# main.net
KiCad netlist of a schematic drawn in Altium Designer
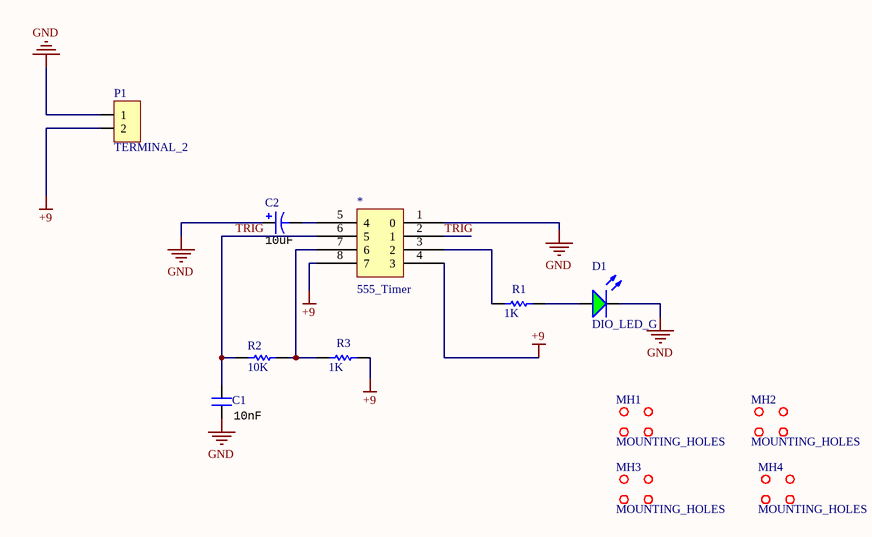
[diagram p0: main.SchDoc]

(export (version "E")
  (design (tool "Eeschema 10.0.6"))
  (components
    (comp (ref "*") (value "555_Timer") (libsource (lib "UWRT_Schematic_Library_2020") (part "555_Timer")))
    (comp (ref "C1")
      (value "10nF")
      (footprint "CAPC0603(1608)55_N")
      (description "CAP CER 10000PF 16V X7R 0603")
      (fields (field (name "MPN") "CC0603KRX7R7BB103") (field (name "MANUFACTURER") "Yageo"))
      (libsource (lib "UWRT_Schematic_Library_2020") (part "CAP_10nF_0603"))
    )
    (comp (ref "C2")
      (value "10uF")
      (footprint "AVX-CAPC3528_V")
      (description "CAP TANT 10UF 20% 10V 1411")
      (fields (field (name "MPN") "F971A106MBAHT3") (field (name "MANUFACTURER") "AVX Corporation"))
      (libsource (lib "UWRT_Schematic_Library_2020") (part "CAP_10uF_1411_POL"))
    )
    (comp (ref "D1")
      (value "DIO_LED_G")
      (footprint "LED_0805_LINE")
      (description "LED GREEN DIFFUSED 0805 SMD")
      (fields (field (name "MPN") "LG R971-KN-1") (field (name "MANUFACTURER") "OSRAM"))
      (libsource (lib "UWRT_Schematic_Library_2020") (part "DIO_LED_G"))
    )
    (comp (ref "MH1")
      (value "MOUNTING_HOLES")
      (footprint "MOUNTING_HOLE")
      (description "6cm x 6cm")
      (libsource (lib "UWRT_Schematic_Library_2020") (part "MOUNTING_HOLES"))
    )
    (comp (ref "MH2")
      (value "MOUNTING_HOLES")
      (footprint "MOUNTING_HOLE")
      (description "6cm x 6cm")
      (libsource (lib "UWRT_Schematic_Library_2020") (part "MOUNTING_HOLES"))
    )
    (comp (ref "MH3")
      (value "MOUNTING_HOLES")
      (footprint "MOUNTING_HOLE")
      (description "6cm x 6cm")
      (libsource (lib "UWRT_Schematic_Library_2020") (part "MOUNTING_HOLES"))
    )
    (comp (ref "MH4")
      (value "MOUNTING_HOLES")
      (footprint "MOUNTING_HOLE")
      (description "6cm x 6cm")
      (libsource (lib "UWRT_Schematic_Library_2020") (part "MOUNTING_HOLES"))
    )
    (comp (ref "P1")
      (value "TERMINAL_2")
      (footprint "OSTYK51102030")
      (description "Header, 2-Pin")
      (fields (field (name "MPN") "OSTYK51102030") (field (name "DIGIKEY PART NUMBER") "ED2953-ND"))
      (libsource (lib "UWRT_Schematic_Library_2020") (part "TERMINAL_2"))
    )
    (comp (ref "R1")
      (value "1K")
      (footprint "RESC0603(1608)_N")
      (description "RES SMD 1K OHM 5% 1/10W 0603")
      (fields (field (name "TOLERANCE") "5%") (field (name "MANUFACTURER") "Yageo"))
      (libsource (lib "UWRT_Schematic_Library_2020") (part "RES_1K_0603"))
    )
    (comp (ref "R2")
      (value "10K")
      (footprint "RESC0603(1608)_N")
      (description "RES SMD 10K OHM 5% 1/10W 0603")
      (fields (field (name "MANUFACTURER") "Yageo") (field (name "MPN") "RC0603JR-0710KL"))
      (libsource (lib "UWRT_Schematic_Library_2020") (part "RES_10K_0603"))
    )
    (comp (ref "R3")
      (value "1K")
      (footprint "RESC0603(1608)_N")
      (description "RES SMD 1K OHM 5% 1/10W 0603")
      (fields (field (name "TOLERANCE") "5%") (field (name "MANUFACTURER") "Yageo"))
      (libsource (lib "UWRT_Schematic_Library_2020") (part "RES_1K_0603"))
    )
  )
  (nets
    (net (code "1") (name "+9") (class "Default")
      (node (ref "*") (pin "4") (pinfunction "3_4") (pintype "passive"))
      (node (ref "*") (pin "8") (pinfunction "7_8") (pintype "passive"))
      (node (ref "P1") (pin "2") (pinfunction "2_2") (pintype "passive"))
      (node (ref "R3") (pin "2") (pinfunction "2_2") (pintype "passive"))
    )
    (net (code "2") (name "/TRIG") (class "Default")
      (node (ref "*") (pin "2") (pinfunction "1_2") (pintype "passive"))
      (node (ref "*") (pin "6") (pinfunction "5_6") (pintype "passive"))
      (node (ref "C1") (pin "2") (pinfunction "2_2") (pintype "passive"))
      (node (ref "R2") (pin "1") (pinfunction "1_1") (pintype "passive"))
    )
    (net (code "3") (name "GND") (class "Default")
      (node (ref "*") (pin "1") (pinfunction "0_1") (pintype "passive"))
      (node (ref "C1") (pin "1") (pinfunction "1_1") (pintype "passive"))
      (node (ref "C2") (pin "1") (pinfunction "1_1") (pintype "passive"))
      (node (ref "D1") (pin "2") (pinfunction "K_2") (pintype "passive"))
      (node (ref "P1") (pin "1") (pinfunction "1_1") (pintype "passive"))
    )
    (net (code "4") (name "Net-(*-2)") (class "Default")
      (node (ref "*") (pin "3") (pinfunction "2_3") (pintype "passive"))
      (node (ref "R1") (pin "1") (pinfunction "1_1") (pintype "passive"))
    )
    (net (code "5") (name "Net-(*-4)") (class "Default")
      (node (ref "*") (pin "5") (pinfunction "4_5") (pintype "passive"))
      (node (ref "C2") (pin "2") (pinfunction "2_2") (pintype "passive"))
    )
    (net (code "6") (name "Net-(*-6)") (class "Default")
      (node (ref "*") (pin "7") (pinfunction "6_7") (pintype "passive"))
      (node (ref "R2") (pin "2") (pinfunction "2_2") (pintype "passive"))
      (node (ref "R3") (pin "1") (pinfunction "1_1") (pintype "passive"))
    )
    (net (code "7") (name "Net-(D1-A)") (class "Default")
      (node (ref "D1") (pin "1") (pinfunction "A_1") (pintype "passive"))
      (node (ref "R1") (pin "2") (pinfunction "2_2") (pintype "passive"))
    )
  )
)
